# carrier_board.net
KiCad netlist of a schematic drawn in Altium Designer
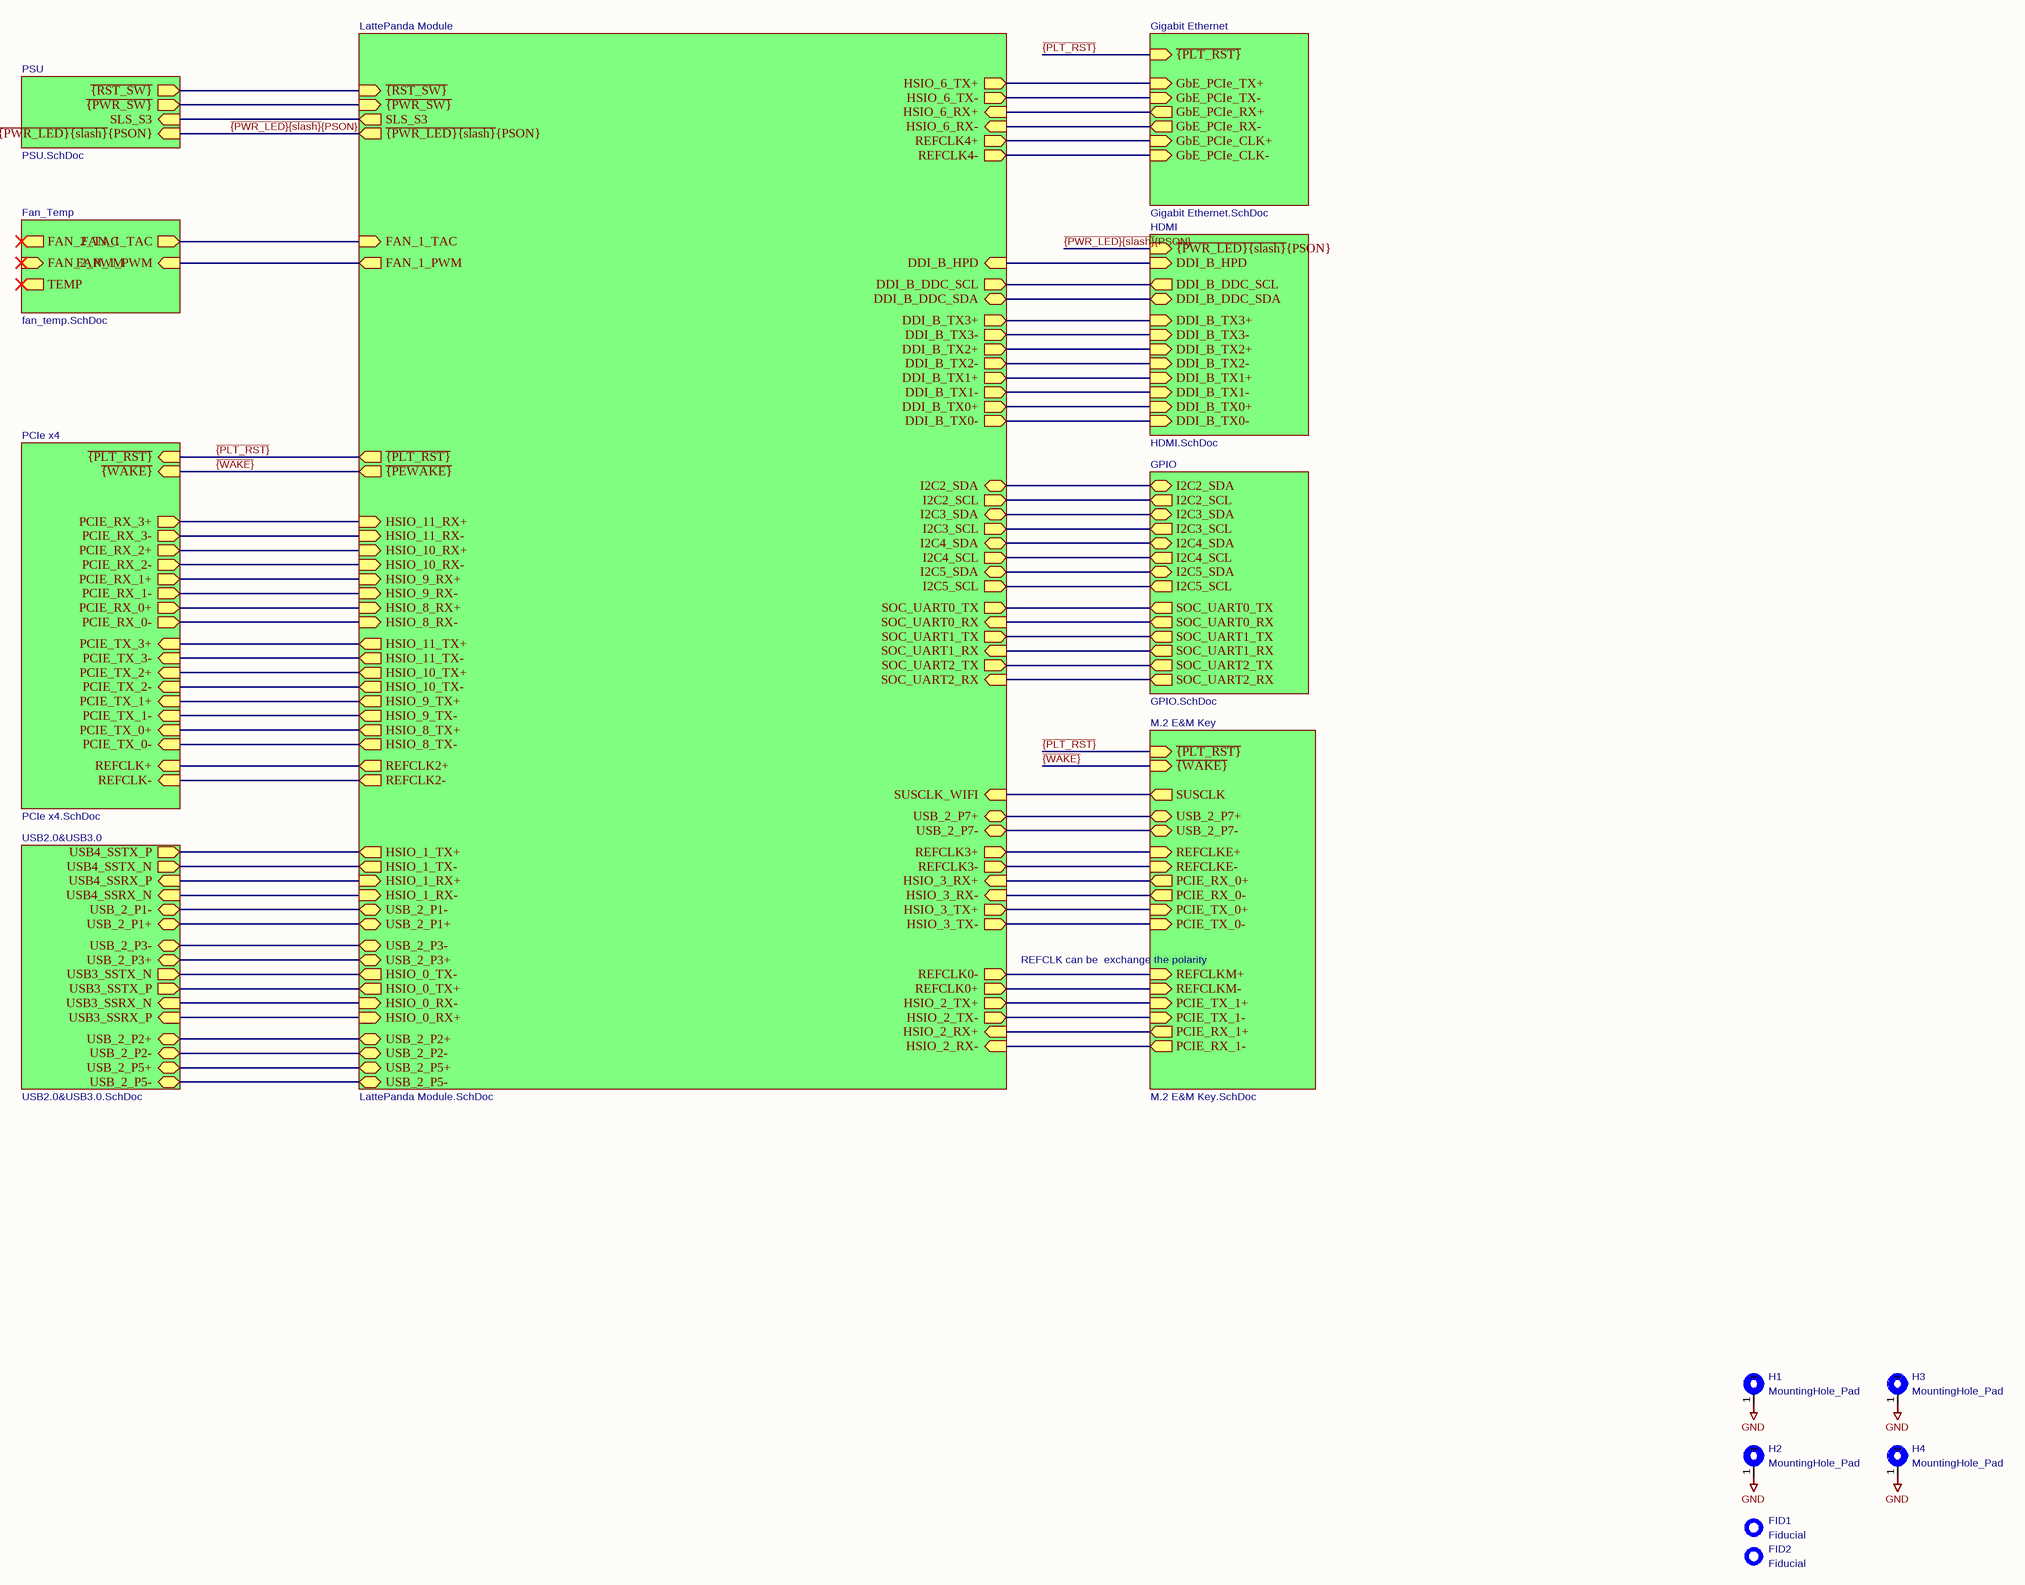
[diagram p0: carrier_board.SchDoc]

(export (version "E")
  (design (tool "Eeschema 10.0.6"))
  (components
    (comp (ref "FID1") (value "Fiducial") (libsource (lib "Mechanical") (part "Fiducial")))
    (comp (ref "FID2") (value "Fiducial") (libsource (lib "Mechanical") (part "Fiducial")))
    (comp (ref "H1") (value "MountingHole_Pad") (libsource (lib "Mechanical") (part "MountingHole_Pad")))
    (comp (ref "H2") (value "MountingHole_Pad") (libsource (lib "Mechanical") (part "MountingHole_Pad")))
    (comp (ref "H3") (value "MountingHole_Pad") (libsource (lib "Mechanical") (part "MountingHole_Pad")))
    (comp (ref "H4") (value "MountingHole_Pad") (libsource (lib "Mechanical") (part "MountingHole_Pad")))
  )
  (nets
    (net (code "92") (name "GND") (class "Default")
      (node (ref "H1") (pin "1") (pinfunction "1_1") (pintype "passive"))
      (node (ref "H2") (pin "1") (pinfunction "1_1") (pintype "passive"))
      (node (ref "H3") (pin "1") (pinfunction "1_1") (pintype "passive"))
      (node (ref "H4") (pin "1") (pinfunction "1_1") (pintype "passive"))
    )
  )
)
